# LightStickAccelerometer.net
KiCad netlist of a schematic drawn in EAGLE
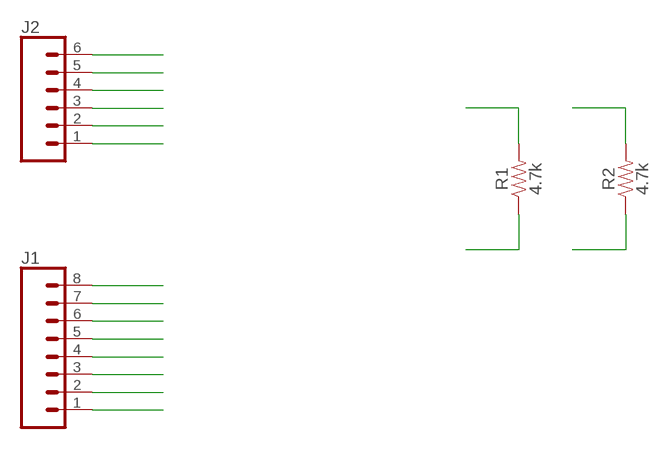
[diagram p0: schematic, sheet 1]

(export (version "E")
  (design (tool "Eeschema 10.0.6"))
  (components
    (comp (ref "J1")
      (value "CONN_08\"")
      (footprint "eagle-import:1X08")
      (libsource (lib "eagle-import") (part "CONN_08{dblquote}"))
    )
    (comp (ref "J2")
      (value "CONN_06SILK_FEMALE_PTH")
      (footprint "eagle-import:1X06")
      (libsource (lib "eagle-import") (part "CONN_06SILK_FEMALE_PTH"))
    )
    (comp (ref "R1")
      (value "4.7k")
      (footprint "eagle-import:0603")
      (libsource (lib "eagle-import") (part "4.7KOHM-0603-1/10W-1%"))
    )
    (comp (ref "R2")
      (value "4.7k")
      (footprint "eagle-import:0603")
      (libsource (lib "eagle-import") (part "4.7KOHM-0603-1/10W-1%"))
    )
  )
  (nets
    (net (code "1") (name "/GND") (class "Default")
      (node (ref "J1") (pin "2") (pinfunction "2_2") (pintype "passive"))
      (node (ref "J1") (pin "8") (pinfunction "8_8") (pintype "passive"))
      (node (ref "J2") (pin "6") (pinfunction "6_6") (pintype "passive"))
    )
    (net (code "2") (name "/INT1") (class "Default")
      (node (ref "J1") (pin "5") (pinfunction "5_5") (pintype "passive"))
      (node (ref "J2") (pin "5") (pinfunction "5_5") (pintype "passive"))
    )
    (net (code "3") (name "/INT2") (class "Default")
      (node (ref "J1") (pin "4") (pinfunction "4_4") (pintype "passive"))
      (node (ref "J2") (pin "4") (pinfunction "4_4") (pintype "passive"))
    )
    (net (code "4") (name "/SCL") (class "Default")
      (node (ref "J1") (pin "6") (pinfunction "6_6") (pintype "passive"))
      (node (ref "J2") (pin "2") (pinfunction "2_2") (pintype "passive"))
      (node (ref "R2") (pin "1") (pinfunction "1_1") (pintype "passive"))
    )
    (net (code "5") (name "/SDA") (class "Default")
      (node (ref "J1") (pin "7") (pinfunction "7_7") (pintype "passive"))
      (node (ref "J2") (pin "3") (pinfunction "3_3") (pintype "passive"))
      (node (ref "R1") (pin "1") (pinfunction "1_1") (pintype "passive"))
    )
    (net (code "6") (name "/VIN") (class "Default")
      (node (ref "J1") (pin "1") (pinfunction "1_1") (pintype "passive"))
      (node (ref "J2") (pin "1") (pinfunction "1_1") (pintype "passive"))
      (node (ref "R1") (pin "2") (pinfunction "2_2") (pintype "passive"))
      (node (ref "R2") (pin "2") (pinfunction "2_2") (pintype "passive"))
    )
    (net (code "7") (name "unconnected-(J1-Pad3)") (class "Default")
      (node (ref "J1") (pin "3") (pinfunction "3_3") (pintype "passive"))
    )
  )
)
